# Control_Module_IO.net
KiCad netlist of a schematic drawn in Altium Designer
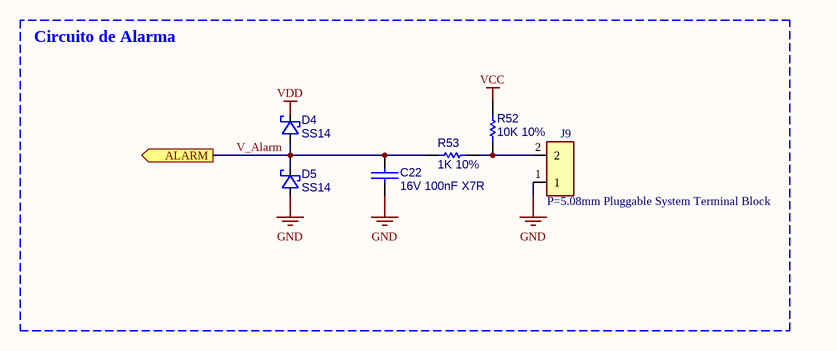
[diagram p0: Control_Module_IO.SchDoc]

(export (version "E")
  (design (tool "Eeschema 10.0.6"))
  (components
    (comp (ref "C22")
      (value "16V 100nF X7R")
      (footprint "CAP0402")
      (description "Non Polarized Capacitor")
      (libsource (lib "Control_Module_Symbols") (part "CAP"))
    )
    (comp (ref "D4")
      (value "SS14")
      (footprint "D_SMA")
      (description "Diode Shottky")
      (libsource (lib "Control_Module_Symbols") (part "DIODO_SH"))
    )
    (comp (ref "D5")
      (value "SS14")
      (footprint "D_SMA")
      (description "Diode Shottky")
      (libsource (lib "Control_Module_Symbols") (part "DIODO_SH"))
    )
    (comp (ref "J9")
      (value "P=5.08mm Pluggable System Terminal Block")
      (footprint "TerminalBlock_1x2_P5mm")
      (description "Alarm Connector")
      (libsource (lib "Control_Module_Symbols") (part "CONN_2P"))
    )
    (comp (ref "R52")
      (value "10K 10%")
      (footprint "RES0402")
      (description "Resistor")
      (libsource (lib "Control_Module_Symbols") (part "Res1"))
    )
    (comp (ref "R53")
      (value "1K 10%")
      (footprint "RES0402")
      (description "Resistor")
      (libsource (lib "Control_Module_Symbols") (part "Res1"))
    )
  )
  (nets
    (net (code "1") (name "/V_Alarm") (class "Default")
      (node (ref "C22") (pin "1") (pinfunction "1_1") (pintype "passive"))
      (node (ref "D4") (pin "1") (pinfunction "A_1") (pintype "passive"))
      (node (ref "D5") (pin "2") (pinfunction "K_2") (pintype "passive"))
      (node (ref "R53") (pin "1") (pinfunction "1_1") (pintype "passive"))
    )
    (net (code "2") (name "GND") (class "Default")
      (node (ref "C22") (pin "2") (pinfunction "2_2") (pintype "passive"))
      (node (ref "D5") (pin "1") (pinfunction "A_1") (pintype "passive"))
      (node (ref "J9") (pin "1") (pinfunction "1_1") (pintype "passive"))
    )
    (net (code "3") (name "Net-(J9-Pad2)") (class "Default")
      (node (ref "J9") (pin "2") (pinfunction "2_2") (pintype "passive"))
      (node (ref "R52") (pin "2") (pinfunction "2_2") (pintype "passive"))
      (node (ref "R53") (pin "2") (pinfunction "2_2") (pintype "passive"))
    )
    (net (code "4") (name "VCC") (class "Default")
      (node (ref "R52") (pin "1") (pinfunction "1_1") (pintype "passive"))
    )
    (net (code "5") (name "VDD") (class "Default")
      (node (ref "D4") (pin "2") (pinfunction "K_2") (pintype "passive"))
    )
  )
)
